# LLA.net
KiCad netlist of a schematic drawn in Altium Designer
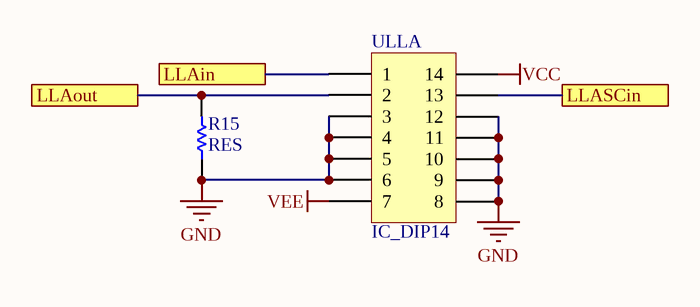
[diagram p0: LLA.SchDoc]

(export (version "E")
  (design (tool "Eeschema 10.0.6"))
  (components
    (comp (ref "R15") (value "RES") (footprint "1206") (libsource (lib "LIBEBAL") (part "RES")))
    (comp (ref "ULLA") (value "IC_DIP14") (footprint "D014_M") (libsource (lib "LIBEBAL") (part "IC_DIP14")))
  )
  (nets
    (net (code "1") (name "/LLASCin") (class "Default")
      (node (ref "ULLA") (pin "13") (pinfunction "13_13") (pintype "passive"))
    )
    (net (code "2") (name "/LLAin") (class "Default")
      (node (ref "ULLA") (pin "1") (pinfunction "1_1") (pintype "passive"))
    )
    (net (code "3") (name "/LLAout") (class "Default")
      (node (ref "R15") (pin "2") (pinfunction "2_2") (pintype "passive"))
      (node (ref "ULLA") (pin "2") (pinfunction "2_2") (pintype "passive"))
    )
    (net (code "4") (name "GND") (class "Default")
      (node (ref "R15") (pin "1") (pinfunction "1_1") (pintype "passive"))
      (node (ref "ULLA") (pin "10") (pinfunction "10_10") (pintype "passive"))
      (node (ref "ULLA") (pin "11") (pinfunction "11_11") (pintype "passive"))
      (node (ref "ULLA") (pin "12") (pinfunction "12_12") (pintype "passive"))
      (node (ref "ULLA") (pin "3") (pinfunction "3_3") (pintype "passive"))
      (node (ref "ULLA") (pin "4") (pinfunction "4_4") (pintype "passive"))
      (node (ref "ULLA") (pin "5") (pinfunction "5_5") (pintype "passive"))
      (node (ref "ULLA") (pin "6") (pinfunction "6_6") (pintype "passive"))
      (node (ref "ULLA") (pin "8") (pinfunction "8_8") (pintype "passive"))
      (node (ref "ULLA") (pin "9") (pinfunction "9_9") (pintype "passive"))
    )
    (net (code "5") (name "VCC") (class "Default")
      (node (ref "ULLA") (pin "14") (pinfunction "14_14") (pintype "passive"))
    )
    (net (code "6") (name "VEE") (class "Default")
      (node (ref "ULLA") (pin "7") (pinfunction "7_7") (pintype "passive"))
    )
  )
)
